# Flipper-AVR-ATTiny.net
KiCad netlist of a schematic drawn in EAGLE
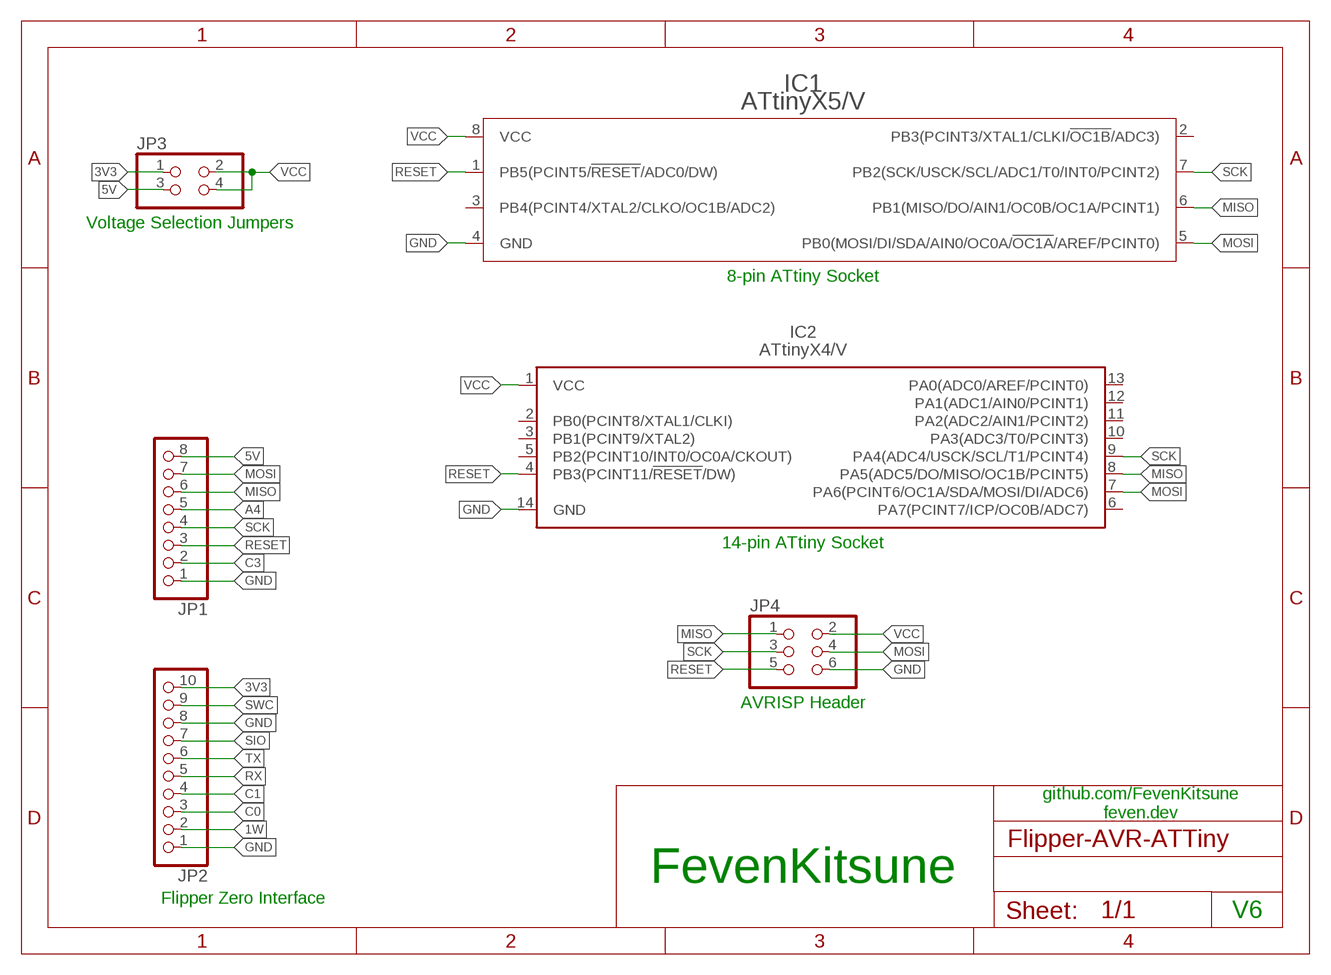
[diagram p0: schematic, sheet 1]

(export (version "E")
  (design (tool "Eeschema 10.0.6"))
  (components
    (comp (ref "IC1")
      (value "ATtinyX5/V")
      (footprint "eagle-import:DIP787W55P254L958H533Q8B-8P3")
      (fields (field (name "MANUFACTURER") "Microchip Technology") (field (name "MPN") "ATtiny85V-10PU"))
      (libsource (lib "eagle-import") (part "ATTINY-8PIN_PDIP85V-10PU"))
    )
    (comp (ref "IC2")
      (value "ATtinyX4/V")
      (footprint "eagle-import:DIP762W55P254L1917H533Q14B")
      (fields (field (name "MANUFACTURER") "Microchip Technology") (field (name "MPN") "ATtiny84V-10PU"))
      (libsource (lib "eagle-import") (part "ATTINY-14PIN_PDIP84V-10PU"))
    )
    (comp (ref "JP1")
      (value "PINHD-1X8")
      (footprint "eagle-import:1X08")
      (libsource (lib "eagle-import") (part "PINHD-1X8"))
    )
    (comp (ref "JP2")
      (value "PINHD-1X10")
      (footprint "eagle-import:1X10")
      (libsource (lib "eagle-import") (part "PINHD-1X10"))
    )
    (comp (ref "JP3")
      (value "PINHD-2X2")
      (footprint "eagle-import:2X02")
      (libsource (lib "eagle-import") (part "PINHD-2X2"))
    )
    (comp (ref "JP4")
      (value "PINHD-2X3")
      (footprint "eagle-import:2X03")
      (libsource (lib "eagle-import") (part "PINHD-2X3"))
    )
  )
  (nets
    (net (code "1") (name "1W") (class "Default")
      (node (ref "JP2") (pin "2") (pinfunction "2_2") (pintype "passive"))
    )
    (net (code "2") (name "3V3") (class "Default")
      (node (ref "JP2") (pin "10") (pinfunction "10_10") (pintype "passive"))
      (node (ref "JP3") (pin "1") (pinfunction "1_1") (pintype "passive"))
    )
    (net (code "3") (name "5V") (class "Default")
      (node (ref "JP1") (pin "8") (pinfunction "8_8") (pintype "passive"))
      (node (ref "JP3") (pin "3") (pinfunction "3_3") (pintype "passive"))
    )
    (net (code "4") (name "A4") (class "Default")
      (node (ref "JP1") (pin "5") (pinfunction "5_5") (pintype "passive"))
    )
    (net (code "5") (name "C0") (class "Default")
      (node (ref "JP2") (pin "3") (pinfunction "3_3") (pintype "passive"))
    )
    (net (code "6") (name "C1") (class "Default")
      (node (ref "JP2") (pin "4") (pinfunction "4_4") (pintype "passive"))
    )
    (net (code "7") (name "C3") (class "Default")
      (node (ref "JP1") (pin "2") (pinfunction "2_2") (pintype "passive"))
    )
    (net (code "8") (name "GND") (class "Default")
      (node (ref "IC1") (pin "4") (pinfunction "GND_4") (pintype "power_in"))
      (node (ref "IC2") (pin "14") (pinfunction "GND_14") (pintype "power_in"))
      (node (ref "JP1") (pin "1") (pinfunction "1_1") (pintype "passive"))
      (node (ref "JP2") (pin "1") (pinfunction "1_1") (pintype "passive"))
      (node (ref "JP2") (pin "8") (pinfunction "8_8") (pintype "passive"))
      (node (ref "JP4") (pin "6") (pinfunction "6_6") (pintype "passive"))
    )
    (net (code "9") (name "MISO") (class "Default")
      (node (ref "IC1") (pin "6") (pinfunction "PB1(MISO/DO/AIN1/OC0B/OC1A/PCINT1)_6") (pintype "bidirectional"))
      (node (ref "IC2") (pin "8") (pinfunction "PA5(ADC5/DO/MISO/OC1B/PCINT5)_8") (pintype "bidirectional"))
      (node (ref "JP1") (pin "6") (pinfunction "6_6") (pintype "passive"))
      (node (ref "JP4") (pin "1") (pinfunction "1_1") (pintype "passive"))
    )
    (net (code "10") (name "MOSI") (class "Default")
      (node (ref "IC1") (pin "5") (pinfunction "PB0(MOSI/DI/SDA/AIN0/OC0A/~{OC1A}/AREF/PCINT0)_5") (pintype "bidirectional"))
      (node (ref "IC2") (pin "7") (pinfunction "PA6(PCINT6/OC1A/SDA/MOSI/DI/ADC6)_7") (pintype "bidirectional"))
      (node (ref "JP1") (pin "7") (pinfunction "7_7") (pintype "passive"))
      (node (ref "JP4") (pin "4") (pinfunction "4_4") (pintype "passive"))
    )
    (net (code "11") (name "RESET") (class "Default")
      (node (ref "IC1") (pin "1") (pinfunction "PB5(PCINT5/~{RESET}/ADC0/DW)_1") (pintype "bidirectional"))
      (node (ref "IC2") (pin "4") (pinfunction "PB3(PCINT11/~{RESET}/DW)_4") (pintype "bidirectional"))
      (node (ref "JP1") (pin "3") (pinfunction "3_3") (pintype "passive"))
      (node (ref "JP4") (pin "5") (pinfunction "5_5") (pintype "passive"))
    )
    (net (code "12") (name "RX") (class "Default")
      (node (ref "JP2") (pin "5") (pinfunction "5_5") (pintype "passive"))
    )
    (net (code "13") (name "SCK") (class "Default")
      (node (ref "IC1") (pin "7") (pinfunction "PB2(SCK/USCK/SCL/ADC1/T0/INT0/PCINT2)_7") (pintype "bidirectional"))
      (node (ref "IC2") (pin "9") (pinfunction "PA4(ADC4/USCK/SCL/T1/PCINT4)_9") (pintype "bidirectional"))
      (node (ref "JP1") (pin "4") (pinfunction "4_4") (pintype "passive"))
      (node (ref "JP4") (pin "3") (pinfunction "3_3") (pintype "passive"))
    )
    (net (code "14") (name "SIO") (class "Default")
      (node (ref "JP2") (pin "7") (pinfunction "7_7") (pintype "passive"))
    )
    (net (code "15") (name "SWC") (class "Default")
      (node (ref "JP2") (pin "9") (pinfunction "9_9") (pintype "passive"))
    )
    (net (code "16") (name "TX") (class "Default")
      (node (ref "JP2") (pin "6") (pinfunction "6_6") (pintype "passive"))
    )
    (net (code "17") (name "VCC") (class "Default")
      (node (ref "IC1") (pin "8") (pinfunction "VCC_8") (pintype "power_in"))
      (node (ref "IC2") (pin "1") (pinfunction "VCC_1") (pintype "power_in"))
      (node (ref "JP3") (pin "2") (pinfunction "2_2") (pintype "passive"))
      (node (ref "JP3") (pin "4") (pinfunction "4_4") (pintype "passive"))
      (node (ref "JP4") (pin "2") (pinfunction "2_2") (pintype "passive"))
    )
    (net (code "18") (name "unconnected-(IC1-PB3(PCINT3{slash}XTAL1{slash}CLKI{slash}~{OC1B}{slash}ADC3)-Pad2)") (class "Default")
      (node (ref "IC1") (pin "2") (pinfunction "PB3(PCINT3/XTAL1/CLKI/~{OC1B}/ADC3)_2") (pintype "bidirectional"))
    )
    (net (code "19") (name "unconnected-(IC1-PB4(PCINT4{slash}XTAL2{slash}CLKO{slash}OC1B{slash}ADC2)-Pad3)") (class "Default")
      (node (ref "IC1") (pin "3") (pinfunction "PB4(PCINT4/XTAL2/CLKO/OC1B/ADC2)_3") (pintype "bidirectional"))
    )
    (net (code "20") (name "unconnected-(IC2-PA0(ADC0{slash}AREF{slash}PCINT0)-Pad13)") (class "Default")
      (node (ref "IC2") (pin "13") (pinfunction "PA0(ADC0/AREF/PCINT0)_13") (pintype "bidirectional"))
    )
    (net (code "21") (name "unconnected-(IC2-PA1(ADC1{slash}AIN0{slash}PCINT1)-Pad12)") (class "Default")
      (node (ref "IC2") (pin "12") (pinfunction "PA1(ADC1/AIN0/PCINT1)_12") (pintype "bidirectional"))
    )
    (net (code "22") (name "unconnected-(IC2-PA2(ADC2{slash}AIN1{slash}PCINT2)-Pad11)") (class "Default")
      (node (ref "IC2") (pin "11") (pinfunction "PA2(ADC2/AIN1/PCINT2)_11") (pintype "bidirectional"))
    )
    (net (code "23") (name "unconnected-(IC2-PA3(ADC3{slash}T0{slash}PCINT3)-Pad10)") (class "Default")
      (node (ref "IC2") (pin "10") (pinfunction "PA3(ADC3/T0/PCINT3)_10") (pintype "bidirectional"))
    )
    (net (code "24") (name "unconnected-(IC2-PA7(PCINT7{slash}ICP{slash}OC0B{slash}ADC7)-Pad6)") (class "Default")
      (node (ref "IC2") (pin "6") (pinfunction "PA7(PCINT7/ICP/OC0B/ADC7)_6") (pintype "bidirectional"))
    )
    (net (code "25") (name "unconnected-(IC2-PB0(PCINT8{slash}XTAL1{slash}CLKI)-Pad2)") (class "Default")
      (node (ref "IC2") (pin "2") (pinfunction "PB0(PCINT8/XTAL1/CLKI)_2") (pintype "bidirectional"))
    )
    (net (code "26") (name "unconnected-(IC2-PB1(PCINT9{slash}XTAL2)-Pad3)") (class "Default")
      (node (ref "IC2") (pin "3") (pinfunction "PB1(PCINT9/XTAL2)_3") (pintype "bidirectional"))
    )
    (net (code "27") (name "unconnected-(IC2-PB2(PCINT10{slash}INT0{slash}OC0A{slash}CKOUT)-Pad5)") (class "Default")
      (node (ref "IC2") (pin "5") (pinfunction "PB2(PCINT10/INT0/OC0A/CKOUT)_5") (pintype "bidirectional"))
    )
  )
)
